# rf-synthesizer.net
KiCad netlist of a schematic drawn in EAGLE
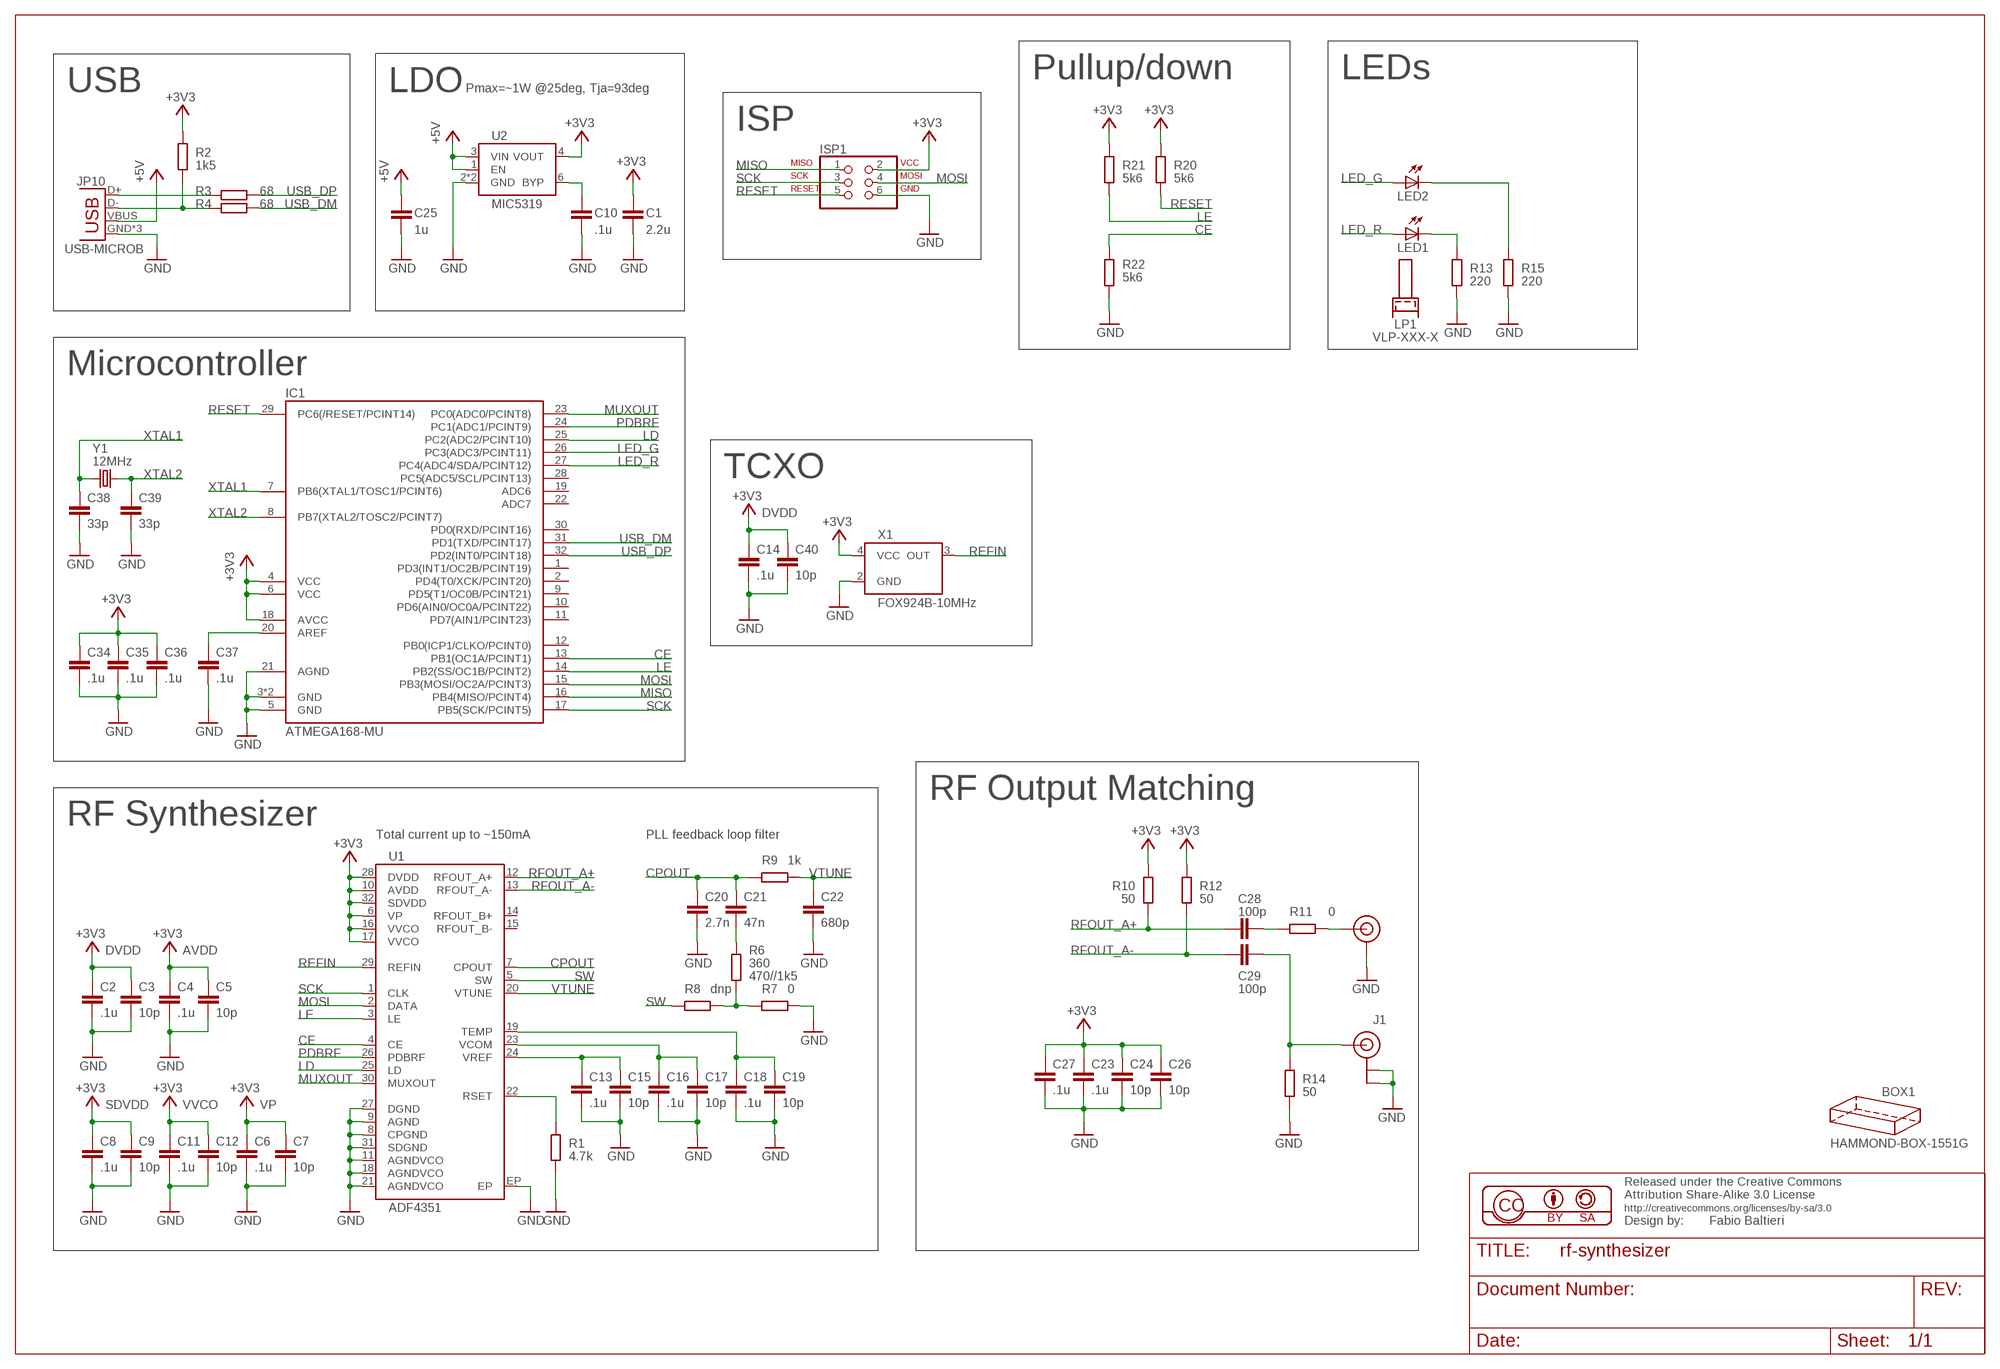
[diagram p0: schematic, sheet 1]

(export (version "E")
  (design (tool "Eeschema 10.0.6"))
  (components
    (comp (ref "BOX1")
      (value "HAMMOND-BOX-1551G")
      (footprint "eagle-import:1551G")
      (libsource (lib "eagle-import") (part "HAMMOND-BOX-1551G"))
    )
    (comp (ref "C1")
      (value "2.2u")
      (footprint "eagle-import:0603")
      (libsource (lib "eagle-import") (part "C0603"))
    )
    (comp (ref "C2")
      (value ".1u")
      (footprint "eagle-import:0603")
      (libsource (lib "eagle-import") (part "C0603"))
    )
    (comp (ref "C3")
      (value "10p")
      (footprint "eagle-import:0603")
      (libsource (lib "eagle-import") (part "C0603"))
    )
    (comp (ref "C4")
      (value ".1u")
      (footprint "eagle-import:0603")
      (libsource (lib "eagle-import") (part "C0603"))
    )
    (comp (ref "C5")
      (value "10p")
      (footprint "eagle-import:0603")
      (libsource (lib "eagle-import") (part "C0603"))
    )
    (comp (ref "C6")
      (value ".1u")
      (footprint "eagle-import:0603")
      (libsource (lib "eagle-import") (part "C0603"))
    )
    (comp (ref "C7")
      (value "10p")
      (footprint "eagle-import:0603")
      (libsource (lib "eagle-import") (part "C0603"))
    )
    (comp (ref "C8")
      (value ".1u")
      (footprint "eagle-import:0603")
      (libsource (lib "eagle-import") (part "C0603"))
    )
    (comp (ref "C9")
      (value "10p")
      (footprint "eagle-import:0603")
      (libsource (lib "eagle-import") (part "C0603"))
    )
    (comp (ref "C10")
      (value ".1u")
      (footprint "eagle-import:0603")
      (libsource (lib "eagle-import") (part "C0603"))
    )
    (comp (ref "C11")
      (value ".1u")
      (footprint "eagle-import:0603")
      (libsource (lib "eagle-import") (part "C0603"))
    )
    (comp (ref "C12")
      (value "10p")
      (footprint "eagle-import:0603")
      (libsource (lib "eagle-import") (part "C0603"))
    )
    (comp (ref "C13")
      (value ".1u")
      (footprint "eagle-import:0603")
      (libsource (lib "eagle-import") (part "C0603"))
    )
    (comp (ref "C14")
      (value ".1u")
      (footprint "eagle-import:0603")
      (libsource (lib "eagle-import") (part "C0603"))
    )
    (comp (ref "C15")
      (value "10p")
      (footprint "eagle-import:0603")
      (libsource (lib "eagle-import") (part "C0603"))
    )
    (comp (ref "C16")
      (value ".1u")
      (footprint "eagle-import:0603")
      (libsource (lib "eagle-import") (part "C0603"))
    )
    (comp (ref "C17")
      (value "10p")
      (footprint "eagle-import:0603")
      (libsource (lib "eagle-import") (part "C0603"))
    )
    (comp (ref "C18")
      (value ".1u")
      (footprint "eagle-import:0603")
      (libsource (lib "eagle-import") (part "C0603"))
    )
    (comp (ref "C19")
      (value "10p")
      (footprint "eagle-import:0603")
      (libsource (lib "eagle-import") (part "C0603"))
    )
    (comp (ref "C20")
      (value "2.7n")
      (footprint "eagle-import:0603")
      (libsource (lib "eagle-import") (part "C0603"))
    )
    (comp (ref "C21")
      (value "47n")
      (footprint "eagle-import:0603")
      (libsource (lib "eagle-import") (part "C0603"))
    )
    (comp (ref "C22")
      (value "680p")
      (footprint "eagle-import:0603")
      (libsource (lib "eagle-import") (part "C0603"))
    )
    (comp (ref "C23")
      (value ".1u")
      (footprint "eagle-import:0603")
      (libsource (lib "eagle-import") (part "C0603"))
    )
    (comp (ref "C24")
      (value "10p")
      (footprint "eagle-import:0603")
      (libsource (lib "eagle-import") (part "C0603"))
    )
    (comp (ref "C25")
      (value "1u")
      (footprint "eagle-import:0603")
      (libsource (lib "eagle-import") (part "C0603"))
    )
    (comp (ref "C26")
      (value "10p")
      (footprint "eagle-import:0603")
      (libsource (lib "eagle-import") (part "C0603"))
    )
    (comp (ref "C27")
      (value ".1u")
      (footprint "eagle-import:0603")
      (libsource (lib "eagle-import") (part "C0603"))
    )
    (comp (ref "C28")
      (value "100p")
      (footprint "eagle-import:0603")
      (libsource (lib "eagle-import") (part "C0603"))
    )
    (comp (ref "C29")
      (value "100p")
      (footprint "eagle-import:0603")
      (libsource (lib "eagle-import") (part "C0603"))
    )
    (comp (ref "C34")
      (value ".1u")
      (footprint "eagle-import:0603")
      (libsource (lib "eagle-import") (part "C0603"))
    )
    (comp (ref "C35")
      (value ".1u")
      (footprint "eagle-import:0603")
      (libsource (lib "eagle-import") (part "C0603"))
    )
    (comp (ref "C36")
      (value ".1u")
      (footprint "eagle-import:0603")
      (libsource (lib "eagle-import") (part "C0603"))
    )
    (comp (ref "C37")
      (value ".1u")
      (footprint "eagle-import:0603")
      (libsource (lib "eagle-import") (part "C0603"))
    )
    (comp (ref "C38")
      (value "33p")
      (footprint "eagle-import:0603")
      (libsource (lib "eagle-import") (part "C0603"))
    )
    (comp (ref "C39")
      (value "33p")
      (footprint "eagle-import:0603")
      (libsource (lib "eagle-import") (part "C0603"))
    )
    (comp (ref "C40")
      (value "10p")
      (footprint "eagle-import:0603")
      (libsource (lib "eagle-import") (part "C0603"))
    )
    (comp (ref "IC1")
      (value "ATMEGA168-MU")
      (footprint "eagle-import:MLF32-TH")
      (libsource (lib "eagle-import") (part "ATMEGA168-MU"))
    )
    (comp (ref "ISP1")
      (value "ISP-AVR910PTH")
      (footprint "eagle-import:2X03")
      (libsource (lib "eagle-import") (part "ISP-AVR910PTH"))
    )
    (comp (ref "J$2")
      (value "SMA_EDGEB")
      (footprint "eagle-import:SMA-EDGE-2")
      (libsource (lib "eagle-import") (part "SMA_EDGEB"))
    )
    (comp (ref "J1")
      (value "U.FL")
      (footprint "eagle-import:U.FL")
      (libsource (lib "eagle-import") (part "U.FL"))
    )
    (comp (ref "JP10")
      (value "USB-MICROB")
      (footprint "eagle-import:USB-MICROB")
      (libsource (lib "eagle-import") (part "USB-MICROB"))
    )
    (comp (ref "LED1")
      (value "LEDSML0805")
      (footprint "eagle-import:SML0805")
      (libsource (lib "eagle-import") (part "LEDSML0805"))
    )
    (comp (ref "LED2")
      (value "LEDSML0805")
      (footprint "eagle-import:SML0805")
      (libsource (lib "eagle-import") (part "LEDSML0805"))
    )
    (comp (ref "LP1")
      (value "VLP-XXX-X")
      (footprint "eagle-import:VLP-XXX-X")
      (libsource (lib "eagle-import") (part "VLP-XXX-X"))
    )
    (comp (ref "R1")
      (value "4.7k")
      (footprint "eagle-import:0603")
      (libsource (lib "eagle-import") (part "R0603"))
    )
    (comp (ref "R2")
      (value "1k5")
      (footprint "eagle-import:0603")
      (libsource (lib "eagle-import") (part "R0603"))
    )
    (comp (ref "R3")
      (value "68")
      (footprint "eagle-import:0603")
      (libsource (lib "eagle-import") (part "R0603"))
    )
    (comp (ref "R4")
      (value "68")
      (footprint "eagle-import:0603")
      (libsource (lib "eagle-import") (part "R0603"))
    )
    (comp (ref "R6")
      (value "360")
      (footprint "eagle-import:0603")
      (libsource (lib "eagle-import") (part "R0603"))
    )
    (comp (ref "R7")
      (value "0")
      (footprint "eagle-import:0603")
      (libsource (lib "eagle-import") (part "R0603"))
    )
    (comp (ref "R8")
      (value "dnp")
      (footprint "eagle-import:0603")
      (libsource (lib "eagle-import") (part "R0603"))
    )
    (comp (ref "R9")
      (value "1k")
      (footprint "eagle-import:0603")
      (libsource (lib "eagle-import") (part "R0603"))
    )
    (comp (ref "R10")
      (value "50")
      (footprint "eagle-import:0603")
      (libsource (lib "eagle-import") (part "R0603"))
    )
    (comp (ref "R11")
      (value "0")
      (footprint "eagle-import:0603")
      (libsource (lib "eagle-import") (part "R0603"))
    )
    (comp (ref "R12")
      (value "50")
      (footprint "eagle-import:0603")
      (libsource (lib "eagle-import") (part "R0603"))
    )
    (comp (ref "R13")
      (value "220")
      (footprint "eagle-import:0603")
      (libsource (lib "eagle-import") (part "R0603"))
    )
    (comp (ref "R14")
      (value "50")
      (footprint "eagle-import:0603")
      (libsource (lib "eagle-import") (part "R0603"))
    )
    (comp (ref "R15")
      (value "220")
      (footprint "eagle-import:0603")
      (libsource (lib "eagle-import") (part "R0603"))
    )
    (comp (ref "R20")
      (value "5k6")
      (footprint "eagle-import:0603")
      (libsource (lib "eagle-import") (part "R0603"))
    )
    (comp (ref "R21")
      (value "5k6")
      (footprint "eagle-import:0603")
      (libsource (lib "eagle-import") (part "R0603"))
    )
    (comp (ref "R22")
      (value "5k6")
      (footprint "eagle-import:0603")
      (libsource (lib "eagle-import") (part "R0603"))
    )
    (comp (ref "U1")
      (value "ADF4351")
      (footprint "eagle-import:LFCSP32")
      (libsource (lib "eagle-import") (part "ADF4351"))
    )
    (comp (ref "U2")
      (value "MIC5319")
      (footprint "eagle-import:MLF6-2X2")
      (libsource (lib "eagle-import") (part "LDO-5PIN"))
    )
    (comp (ref "X1")
      (value "FOX924B-10MHz")
      (footprint "eagle-import:OSC-5X3.2")
      (libsource (lib "eagle-import") (part "OSCILLATOR"))
    )
    (comp (ref "Y1")
      (value "12MHz")
      (footprint "eagle-import:CRYSTAL-SMD-5X3")
      (libsource (lib "eagle-import") (part "CRYSTAL5X3"))
    )
  )
  (nets
    (net (code "1") (name "+3V3") (class "Default")
      (node (ref "C1") (pin "1") (pinfunction "1_1") (pintype "passive"))
      (node (ref "C11") (pin "1") (pinfunction "1_1") (pintype "passive"))
      (node (ref "C12") (pin "1") (pinfunction "1_1") (pintype "passive"))
      (node (ref "C14") (pin "1") (pinfunction "1_1") (pintype "passive"))
      (node (ref "C2") (pin "1") (pinfunction "1_1") (pintype "passive"))
      (node (ref "C23") (pin "1") (pinfunction "1_1") (pintype "passive"))
      (node (ref "C24") (pin "1") (pinfunction "1_1") (pintype "passive"))
      (node (ref "C26") (pin "1") (pinfunction "1_1") (pintype "passive"))
      (node (ref "C27") (pin "1") (pinfunction "1_1") (pintype "passive"))
      (node (ref "C3") (pin "1") (pinfunction "1_1") (pintype "passive"))
      (node (ref "C34") (pin "1") (pinfunction "1_1") (pintype "passive"))
      (node (ref "C35") (pin "1") (pinfunction "1_1") (pintype "passive"))
      (node (ref "C36") (pin "1") (pinfunction "1_1") (pintype "passive"))
      (node (ref "C4") (pin "1") (pinfunction "1_1") (pintype "passive"))
      (node (ref "C40") (pin "1") (pinfunction "1_1") (pintype "passive"))
      (node (ref "C5") (pin "1") (pinfunction "1_1") (pintype "passive"))
      (node (ref "C6") (pin "1") (pinfunction "1_1") (pintype "passive"))
      (node (ref "C7") (pin "1") (pinfunction "1_1") (pintype "passive"))
      (node (ref "C8") (pin "1") (pinfunction "1_1") (pintype "passive"))
      (node (ref "C9") (pin "1") (pinfunction "1_1") (pintype "passive"))
      (node (ref "IC1") (pin "18") (pinfunction "AVCC_18") (pintype "passive"))
      (node (ref "IC1") (pin "4") (pinfunction "VCC_4") (pintype "power_in"))
      (node (ref "IC1") (pin "6") (pinfunction "VCC_6") (pintype "power_in"))
      (node (ref "ISP1") (pin "2") (pinfunction "2_2") (pintype "passive"))
      (node (ref "R10") (pin "1") (pinfunction "1_1") (pintype "passive"))
      (node (ref "R12") (pin "1") (pinfunction "1_1") (pintype "passive"))
      (node (ref "R2") (pin "1") (pinfunction "1_1") (pintype "passive"))
      (node (ref "R20") (pin "1") (pinfunction "1_1") (pintype "passive"))
      (node (ref "R21") (pin "1") (pinfunction "1_1") (pintype "passive"))
      (node (ref "U1") (pin "10") (pinfunction "AVDD_10") (pintype "bidirectional"))
      (node (ref "U1") (pin "16") (pinfunction "VVCO_16") (pintype "bidirectional"))
      (node (ref "U1") (pin "17") (pinfunction "VVCO_17") (pintype "bidirectional"))
      (node (ref "U1") (pin "28") (pinfunction "DVDD_28") (pintype "bidirectional"))
      (node (ref "U1") (pin "32") (pinfunction "SDVDD_32") (pintype "bidirectional"))
      (node (ref "U1") (pin "6") (pinfunction "VP_6") (pintype "bidirectional"))
      (node (ref "U2") (pin "4") (pinfunction "VOUT_4") (pintype "bidirectional"))
      (node (ref "X1") (pin "4") (pinfunction "VCC_4") (pintype "bidirectional"))
    )
    (net (code "2") (name "+5V") (class "Default")
      (node (ref "C25") (pin "1") (pinfunction "1_1") (pintype "passive"))
      (node (ref "JP10") (pin "VBUS") (pinfunction "VBUS_VBUS") (pintype "bidirectional"))
      (node (ref "U2") (pin "1") (pinfunction "EN_1") (pintype "bidirectional"))
      (node (ref "U2") (pin "3") (pinfunction "VIN_3") (pintype "bidirectional"))
    )
    (net (code "3") (name "/CE") (class "Default")
      (node (ref "IC1") (pin "13") (pinfunction "PB1(OC1A/PCINT1)_13") (pintype "bidirectional"))
      (node (ref "R22") (pin "2") (pinfunction "2_2") (pintype "passive"))
      (node (ref "U1") (pin "4") (pinfunction "CE_4") (pintype "bidirectional"))
    )
    (net (code "4") (name "/CPOUT") (class "Default")
      (node (ref "C20") (pin "1") (pinfunction "1_1") (pintype "passive"))
      (node (ref "C21") (pin "1") (pinfunction "1_1") (pintype "passive"))
      (node (ref "R9") (pin "1") (pinfunction "1_1") (pintype "passive"))
      (node (ref "U1") (pin "7") (pinfunction "CPOUT_7") (pintype "bidirectional"))
    )
    (net (code "5") (name "/LD") (class "Default")
      (node (ref "IC1") (pin "25") (pinfunction "PC2(ADC2/PCINT10)_25") (pintype "bidirectional"))
      (node (ref "U1") (pin "25") (pinfunction "LD_25") (pintype "bidirectional"))
    )
    (net (code "6") (name "/LE") (class "Default")
      (node (ref "IC1") (pin "14") (pinfunction "PB2(SS/OC1B/PCINT2)_14") (pintype "bidirectional"))
      (node (ref "R21") (pin "2") (pinfunction "2_2") (pintype "passive"))
      (node (ref "U1") (pin "3") (pinfunction "LE_3") (pintype "bidirectional"))
    )
    (net (code "7") (name "/LED_G") (class "Default")
      (node (ref "IC1") (pin "26") (pinfunction "PC3(ADC3/PCINT11)_26") (pintype "bidirectional"))
      (node (ref "LED2") (pin "A") (pinfunction "A_A") (pintype "passive"))
    )
    (net (code "8") (name "/LED_R") (class "Default")
      (node (ref "IC1") (pin "27") (pinfunction "PC4(ADC4/SDA/PCINT12)_27") (pintype "bidirectional"))
      (node (ref "LED1") (pin "A") (pinfunction "A_A") (pintype "passive"))
    )
    (net (code "9") (name "/MISO") (class "Default")
      (node (ref "IC1") (pin "16") (pinfunction "PB4(MISO/PCINT4)_16") (pintype "bidirectional"))
      (node (ref "ISP1") (pin "1") (pinfunction "1_1") (pintype "passive"))
    )
    (net (code "10") (name "/MOSI") (class "Default")
      (node (ref "IC1") (pin "15") (pinfunction "PB3(MOSI/OC2A/PCINT3)_15") (pintype "bidirectional"))
      (node (ref "ISP1") (pin "4") (pinfunction "4_4") (pintype "passive"))
      (node (ref "U1") (pin "2") (pinfunction "DATA_2") (pintype "bidirectional"))
    )
    (net (code "11") (name "/MUXOUT") (class "Default")
      (node (ref "IC1") (pin "23") (pinfunction "PC0(ADC0/PCINT8)_23") (pintype "bidirectional"))
      (node (ref "U1") (pin "30") (pinfunction "MUXOUT_30") (pintype "bidirectional"))
    )
    (net (code "12") (name "/PDBRF") (class "Default")
      (node (ref "IC1") (pin "24") (pinfunction "PC1(ADC1/PCINT9)_24") (pintype "bidirectional"))
      (node (ref "U1") (pin "26") (pinfunction "PDBRF_26") (pintype "bidirectional"))
    )
    (net (code "13") (name "/REFIN") (class "Default")
      (node (ref "U1") (pin "29") (pinfunction "REFIN_29") (pintype "bidirectional"))
      (node (ref "X1") (pin "3") (pinfunction "OUT_3") (pintype "bidirectional"))
    )
    (net (code "14") (name "/RESET") (class "Default")
      (node (ref "IC1") (pin "29") (pinfunction "PC6(/RESET/PCINT14)_29") (pintype "bidirectional"))
      (node (ref "ISP1") (pin "5") (pinfunction "5_5") (pintype "passive"))
      (node (ref "R20") (pin "2") (pinfunction "2_2") (pintype "passive"))
    )
    (net (code "15") (name "/RFOUT_A+") (class "Default")
      (node (ref "C28") (pin "1") (pinfunction "1_1") (pintype "passive"))
      (node (ref "R10") (pin "2") (pinfunction "2_2") (pintype "passive"))
      (node (ref "U1") (pin "12") (pinfunction "RFOUT_A+_12") (pintype "bidirectional"))
    )
    (net (code "16") (name "/RFOUT_A-") (class "Default")
      (node (ref "C29") (pin "1") (pinfunction "1_1") (pintype "passive"))
      (node (ref "R12") (pin "2") (pinfunction "2_2") (pintype "passive"))
      (node (ref "U1") (pin "13") (pinfunction "RFOUT_A-_13") (pintype "bidirectional"))
    )
    (net (code "17") (name "/SCK") (class "Default")
      (node (ref "IC1") (pin "17") (pinfunction "PB5(SCK/PCINT5)_17") (pintype "bidirectional"))
      (node (ref "ISP1") (pin "3") (pinfunction "3_3") (pintype "passive"))
      (node (ref "U1") (pin "1") (pinfunction "CLK_1") (pintype "bidirectional"))
    )
    (net (code "18") (name "/SW") (class "Default")
      (node (ref "R8") (pin "1") (pinfunction "1_1") (pintype "passive"))
      (node (ref "U1") (pin "5") (pinfunction "SW_5") (pintype "bidirectional"))
    )
    (net (code "19") (name "/USB_DM") (class "Default")
      (node (ref "IC1") (pin "31") (pinfunction "PD1(TXD/PCINT17)_31") (pintype "bidirectional"))
      (node (ref "R4") (pin "2") (pinfunction "2_2") (pintype "passive"))
    )
    (net (code "20") (name "/USB_DP") (class "Default")
      (node (ref "IC1") (pin "32") (pinfunction "PD2(INT0/PCINT18)_32") (pintype "bidirectional"))
      (node (ref "R3") (pin "2") (pinfunction "2_2") (pintype "passive"))
    )
    (net (code "21") (name "/VTUNE") (class "Default")
      (node (ref "C22") (pin "1") (pinfunction "1_1") (pintype "passive"))
      (node (ref "R9") (pin "2") (pinfunction "2_2") (pintype "passive"))
      (node (ref "U1") (pin "20") (pinfunction "VTUNE_20") (pintype "bidirectional"))
    )
    (net (code "22") (name "/XTAL1") (class "Default")
      (node (ref "C38") (pin "1") (pinfunction "1_1") (pintype "passive"))
      (node (ref "IC1") (pin "7") (pinfunction "PB6(XTAL1/TOSC1/PCINT6)_7") (pintype "bidirectional"))
      (node (ref "Y1") (pin "1") (pinfunction "1_1") (pintype "passive"))
    )
    (net (code "23") (name "/XTAL2") (class "Default")
      (node (ref "C39") (pin "1") (pinfunction "1_1") (pintype "passive"))
      (node (ref "IC1") (pin "8") (pinfunction "PB7(XTAL2/TOSC2/PCINT7)_8") (pintype "bidirectional"))
      (node (ref "Y1") (pin "3") (pinfunction "2_3") (pintype "passive"))
    )
    (net (code "24") (name "GND") (class "Default")
      (node (ref "C1") (pin "2") (pinfunction "2_2") (pintype "passive"))
      (node (ref "C10") (pin "2") (pinfunction "2_2") (pintype "passive"))
      (node (ref "C11") (pin "2") (pinfunction "2_2") (pintype "passive"))
      (node (ref "C12") (pin "2") (pinfunction "2_2") (pintype "passive"))
      (node (ref "C13") (pin "2") (pinfunction "2_2") (pintype "passive"))
      (node (ref "C14") (pin "2") (pinfunction "2_2") (pintype "passive"))
      (node (ref "C15") (pin "2") (pinfunction "2_2") (pintype "passive"))
      (node (ref "C16") (pin "2") (pinfunction "2_2") (pintype "passive"))
      (node (ref "C17") (pin "2") (pinfunction "2_2") (pintype "passive"))
      (node (ref "C18") (pin "2") (pinfunction "2_2") (pintype "passive"))
      (node (ref "C19") (pin "2") (pinfunction "2_2") (pintype "passive"))
      (node (ref "C2") (pin "2") (pinfunction "2_2") (pintype "passive"))
      (node (ref "C20") (pin "2") (pinfunction "2_2") (pintype "passive"))
      (node (ref "C22") (pin "2") (pinfunction "2_2") (pintype "passive"))
      (node (ref "C23") (pin "2") (pinfunction "2_2") (pintype "passive"))
      (node (ref "C24") (pin "2") (pinfunction "2_2") (pintype "passive"))
      (node (ref "C25") (pin "2") (pinfunction "2_2") (pintype "passive"))
      (node (ref "C26") (pin "2") (pinfunction "2_2") (pintype "passive"))
      (node (ref "C27") (pin "2") (pinfunction "2_2") (pintype "passive"))
      (node (ref "C3") (pin "2") (pinfunction "2_2") (pintype "passive"))
      (node (ref "C34") (pin "2") (pinfunction "2_2") (pintype "passive"))
      (node (ref "C35") (pin "2") (pinfunction "2_2") (pintype "passive"))
      (node (ref "C36") (pin "2") (pinfunction "2_2") (pintype "passive"))
      (node (ref "C37") (pin "2") (pinfunction "2_2") (pintype "passive"))
      (node (ref "C38") (pin "2") (pinfunction "2_2") (pintype "passive"))
      (node (ref "C39") (pin "2") (pinfunction "2_2") (pintype "passive"))
      (node (ref "C4") (pin "2") (pinfunction "2_2") (pintype "passive"))
      (node (ref "C40") (pin "2") (pinfunction "2_2") (pintype "passive"))
      (node (ref "C5") (pin "2") (pinfunction "2_2") (pintype "passive"))
      (node (ref "C6") (pin "2") (pinfunction "2_2") (pintype "passive"))
      (node (ref "C7") (pin "2") (pinfunction "2_2") (pintype "passive"))
      (node (ref "C8") (pin "2") (pinfunction "2_2") (pintype "passive"))
      (node (ref "C9") (pin "2") (pinfunction "2_2") (pintype "passive"))
      (node (ref "IC1") (pin "21") (pinfunction "AGND_21") (pintype "power_in"))
      (node (ref "IC1") (pin "3") (pinfunction "GND_3") (pintype "power_in"))
      (node (ref "IC1") (pin "5") (pinfunction "GND_5") (pintype "power_in"))
      (node (ref "IC1") (pin "TH") (pinfunction "GND_TH") (pintype "power_in"))
      (node (ref "ISP1") (pin "6") (pinfunction "6_6") (pintype "passive"))
      (node (ref "J$2") (pin "M1") (pinfunction "GND_M1") (pintype "bidirectional"))
      (node (ref "J$2") (pin "M2") (pinfunction "GND_M2") (pintype "bidirectional"))
      (node (ref "J$2") (pin "M3") (pinfunction "GND_M3") (pintype "bidirectional"))
      (node (ref "J$2") (pin "M4") (pinfunction "GND_M4") (pintype "bidirectional"))
      (node (ref "J1") (pin "P$1") (pinfunction "GND_P$1") (pintype "bidirectional"))
      (node (ref "J1") (pin "P$2") (pinfunction "GND_P$2") (pintype "bidirectional"))
      (node (ref "JP10") (pin "GND") (pinfunction "GND_GND") (pintype "bidirectional"))
      (node (ref "JP10") (pin "MT1") (pinfunction "GND_MT1") (pintype "bidirectional"))
      (node (ref "JP10") (pin "MT2") (pinfunction "GND_MT2") (pintype "bidirectional"))
      (node (ref "R1") (pin "2") (pinfunction "2_2") (pintype "passive"))
      (node (ref "R13") (pin "1") (pinfunction "1_1") (pintype "passive"))
      (node (ref "R14") (pin "2") (pinfunction "2_2") (pintype "passive"))
      (node (ref "R15") (pin "1") (pinfunction "1_1") (pintype "passive"))
      (node (ref "R22") (pin "1") (pinfunction "1_1") (pintype "passive"))
      (node (ref "R7") (pin "2") (pinfunction "2_2") (pintype "passive"))
      (node (ref "U1") (pin "11") (pinfunction "AGNDVCO_11") (pintype "bidirectional"))
      (node (ref "U1") (pin "18") (pinfunction "AGNDVCO_18") (pintype "bidirectional"))
      (node (ref "U1") (pin "21") (pinfunction "AGNDVCO_21") (pintype "bidirectional"))
      (node (ref "U1") (pin "27") (pinfunction "DGND_27") (pintype "bidirectional"))
      (node (ref "U1") (pin "31") (pinfunction "SDGND_31") (pintype "bidirectional"))
      (node (ref "U1") (pin "8") (pinfunction "CPGND_8") (pintype "bidirectional"))
      (node (ref "U1") (pin "9") (pinfunction "AGND_9") (pintype "bidirectional"))
      (node (ref "U1") (pin "EP") (pinfunction "EP_EP") (pintype "bidirectional"))
      (node (ref "U2") (pin "2") (pinfunction "GND_2") (pintype "bidirectional"))
      (node (ref "U2") (pin "TH") (pinfunction "GND_TH") (pintype "bidirectional"))
      (node (ref "X1") (pin "2") (pinfunction "GND_2") (pintype "bidirectional"))
    )
    (net (code "25") (name "Net-(C21-Pad2)") (class "Default")
      (node (ref "C21") (pin "2") (pinfunction "2_2") (pintype "passive"))
      (node (ref "R6") (pin "1") (pinfunction "1_1") (pintype "passive"))
    )
    (net (code "26") (name "Net-(C28-Pad2)") (class "Default")
      (node (ref "C28") (pin "2") (pinfunction "2_2") (pintype "passive"))
      (node (ref "R11") (pin "1") (pinfunction "1_1") (pintype "passive"))
    )
    (net (code "27") (name "Net-(IC1-AREF)") (class "Default")
      (node (ref "C37") (pin "1") (pinfunction "1_1") (pintype "passive"))
      (node (ref "IC1") (pin "20") (pinfunction "AREF_20") (pintype "passive"))
    )
    (net (code "28") (name "Net-(J$2-PadFEED)") (class "Default")
      (node (ref "J$2") (pin "FEED") (pinfunction "FEED_FEED") (pintype "bidirectional"))
      (node (ref "R11") (pin "2") (pinfunction "2_2") (pintype "passive"))
    )
    (net (code "29") (name "Net-(J1-SIGNAL)") (class "Default")
      (node (ref "C29") (pin "2") (pinfunction "2_2") (pintype "passive"))
      (node (ref "J1") (pin "P$3") (pinfunction "SIGNAL_P$3") (pintype "bidirectional"))
      (node (ref "R14") (pin "1") (pinfunction "1_1") (pintype "passive"))
    )
    (net (code "30") (name "Net-(JP10-PadD+)") (class "Default")
      (node (ref "JP10") (pin "D+") (pinfunction "D+_D+") (pintype "bidirectional"))
      (node (ref "R3") (pin "1") (pinfunction "1_1") (pintype "passive"))
    )
    (net (code "31") (name "Net-(JP10-PadD-)") (class "Default")
      (node (ref "JP10") (pin "D-") (pinfunction "D-_D-") (pintype "bidirectional"))
      (node (ref "R2") (pin "2") (pinfunction "2_2") (pintype "passive"))
      (node (ref "R4") (pin "1") (pinfunction "1_1") (pintype "passive"))
    )
    (net (code "32") (name "Net-(LED1-PadC)") (class "Default")
      (node (ref "LED1") (pin "C") (pinfunction "C_C") (pintype "passive"))
      (node (ref "R13") (pin "2") (pinfunction "2_2") (pintype "passive"))
    )
    (net (code "33") (name "Net-(LED2-PadC)") (class "Default")
      (node (ref "LED2") (pin "C") (pinfunction "C_C") (pintype "passive"))
      (node (ref "R15") (pin "2") (pinfunction "2_2") (pintype "passive"))
    )
    (net (code "34") (name "Net-(R6-Pad2)") (class "Default")
      (node (ref "R6") (pin "2") (pinfunction "2_2") (pintype "passive"))
      (node (ref "R7") (pin "1") (pinfunction "1_1") (pintype "passive"))
      (node (ref "R8") (pin "2") (pinfunction "2_2") (pintype "passive"))
    )
    (net (code "35") (name "Net-(U1-RSET)") (class "Default")
      (node (ref "R1") (pin "1") (pinfunction "1_1") (pintype "passive"))
      (node (ref "U1") (pin "22") (pinfunction "RSET_22") (pintype "bidirectional"))
    )
    (net (code "36") (name "Net-(U1-TEMP)") (class "Default")
      (node (ref "C18") (pin "1") (pinfunction "1_1") (pintype "passive"))
      (node (ref "C19") (pin "1") (pinfunction "1_1") (pintype "passive"))
      (node (ref "U1") (pin "19") (pinfunction "TEMP_19") (pintype "bidirectional"))
    )
    (net (code "37") (name "Net-(U1-VCOM)") (class "Default")
      (node (ref "C16") (pin "1") (pinfunction "1_1") (pintype "passive"))
      (node (ref "C17") (pin "1") (pinfunction "1_1") (pintype "passive"))
      (node (ref "U1") (pin "23") (pinfunction "VCOM_23") (pintype "bidirectional"))
    )
    (net (code "38") (name "Net-(U1-VREF)") (class "Default")
      (node (ref "C13") (pin "1") (pinfunction "1_1") (pintype "passive"))
      (node (ref "C15") (pin "1") (pinfunction "1_1") (pintype "passive"))
      (node (ref "U1") (pin "24") (pinfunction "VREF_24") (pintype "bidirectional"))
    )
    (net (code "39") (name "Net-(U2-BYP)") (class "Default")
      (node (ref "C10") (pin "1") (pinfunction "1_1") (pintype "passive"))
      (node (ref "U2") (pin "6") (pinfunction "BYP_6") (pintype "bidirectional"))
    )
    (net (code "40") (name "unconnected-(IC1-ADC6-Pad19)") (class "Default")
      (node (ref "IC1") (pin "19") (pinfunction "ADC6_19") (pintype "passive"))
    )
    (net (code "41") (name "unconnected-(IC1-ADC7-Pad22)") (class "Default")
      (node (ref "IC1") (pin "22") (pinfunction "ADC7_22") (pintype "passive"))
    )
    (net (code "42") (name "unconnected-(IC1-PB0(ICP1{slash}CLKO{slash}PCINT0)-Pad12)") (class "Default")
      (node (ref "IC1") (pin "12") (pinfunction "PB0(ICP1/CLKO/PCINT0)_12") (pintype "bidirectional"))
    )
    (net (code "43") (name "unconnected-(IC1-PC5(ADC5{slash}SCL{slash}PCINT13)-Pad28)") (class "Default")
      (node (ref "IC1") (pin "28") (pinfunction "PC5(ADC5/SCL/PCINT13)_28") (pintype "bidirectional"))
    )
    (net (code "44") (name "unconnected-(IC1-PD0(RXD{slash}PCINT16)-Pad30)") (class "Default")
      (node (ref "IC1") (pin "30") (pinfunction "PD0(RXD/PCINT16)_30") (pintype "bidirectional"))
    )
    (net (code "45") (name "unconnected-(IC1-PD3(INT1{slash}OC2B{slash}PCINT19)-Pad1)") (class "Default")
      (node (ref "IC1") (pin "1") (pinfunction "PD3(INT1/OC2B/PCINT19)_1") (pintype "bidirectional"))
    )
    (net (code "46") (name "unconnected-(IC1-PD4(T0{slash}XCK{slash}PCINT20)-Pad2)") (class "Default")
      (node (ref "IC1") (pin "2") (pinfunction "PD4(T0/XCK/PCINT20)_2") (pintype "bidirectional"))
    )
    (net (code "47") (name "unconnected-(IC1-PD5(T1{slash}OC0B{slash}PCINT21)-Pad9)") (class "Default")
      (node (ref "IC1") (pin "9") (pinfunction "PD5(T1/OC0B/PCINT21)_9") (pintype "bidirectional"))
    )
    (net (code "48") (name "unconnected-(IC1-PD6(AIN0{slash}OC0A{slash}PCINT22)-Pad10)") (class "Default")
      (node (ref "IC1") (pin "10") (pinfunction "PD6(AIN0/OC0A/PCINT22)_10") (pintype "bidirectional"))
    )
    (net (code "49") (name "unconnected-(IC1-PD7(AIN1{slash}PCINT23)-Pad11)") (class "Default")
      (node (ref "IC1") (pin "11") (pinfunction "PD7(AIN1/PCINT23)_11") (pintype "bidirectional"))
    )
    (net (code "50") (name "unconnected-(U1-RFOUT_B+-Pad14)") (class "Default")
      (node (ref "U1") (pin "14") (pinfunction "RFOUT_B+_14") (pintype "bidirectional"))
    )
    (net (code "51") (name "unconnected-(U1-RFOUT_B--Pad15)") (class "Default")
      (node (ref "U1") (pin "15") (pinfunction "RFOUT_B-_15") (pintype "bidirectional"))
    )
  )
)
